# DMG_Control_Panel.net
KiCad netlist of a schematic drawn in EAGLE
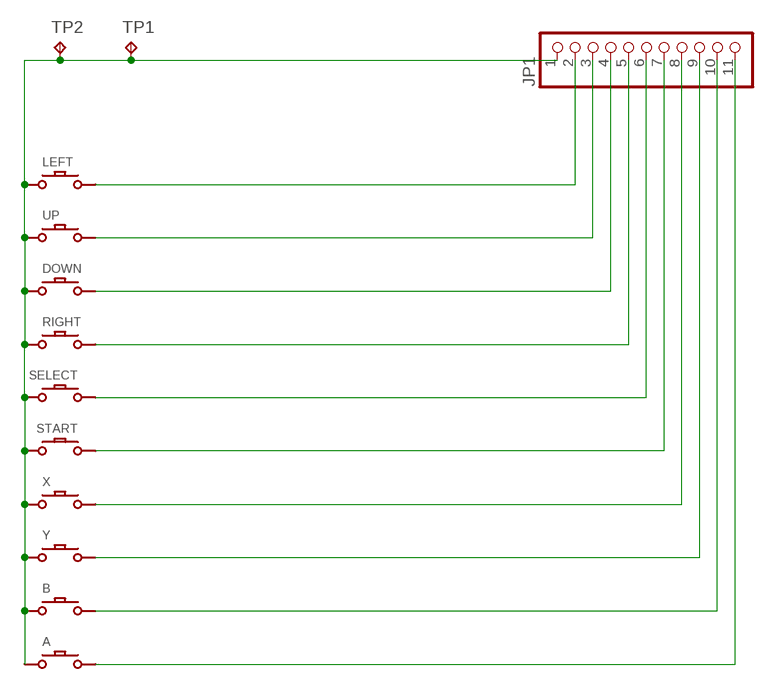
[diagram p0: schematic, sheet 1]

(export (version "E")
  (design (tool "Eeschema 10.0.6"))
  (components
    (comp (ref "A")
      (value "DMG-BTN")
      (footprint "eagle-import:DMG-BTN")
      (libsource (lib "eagle-import") (part "DMG-BTNREGULAR"))
    )
    (comp (ref "B")
      (value "DMG-BTN")
      (footprint "eagle-import:DMG-BTN")
      (libsource (lib "eagle-import") (part "DMG-BTNREGULAR"))
    )
    (comp (ref "DOWN")
      (value "DMG-BTN")
      (footprint "eagle-import:DMG-BTN")
      (libsource (lib "eagle-import") (part "DMG-BTNREGULAR"))
    )
    (comp (ref "JP1")
      (value "PINHD-1X11M")
      (footprint "eagle-import:1X11M")
      (libsource (lib "eagle-import") (part "PINHD-1X11M"))
    )
    (comp (ref "LEFT")
      (value "DMG-BTN")
      (footprint "eagle-import:DMG-BTN")
      (libsource (lib "eagle-import") (part "DMG-BTNREGULAR"))
    )
    (comp (ref "RIGHT")
      (value "DMG-BTN")
      (footprint "eagle-import:DMG-BTN")
      (libsource (lib "eagle-import") (part "DMG-BTNREGULAR"))
    )
    (comp (ref "SELECT")
      (value "DMG-BTN")
      (footprint "eagle-import:DMG-SEL")
      (libsource (lib "eagle-import") (part "DMG-BTNSELECT"))
    )
    (comp (ref "START")
      (value "DMG-BTN")
      (footprint "eagle-import:DMG-SEL")
      (libsource (lib "eagle-import") (part "DMG-BTNSELECT"))
    )
    (comp (ref "TP1")
      (value "TPPAD1-13Y")
      (footprint "eagle-import:P1-13Y")
      (libsource (lib "eagle-import") (part "TPPAD1-13Y"))
    )
    (comp (ref "TP2")
      (value "TPPAD1-13Y")
      (footprint "eagle-import:P1-13Y")
      (libsource (lib "eagle-import") (part "TPPAD1-13Y"))
    )
    (comp (ref "UP")
      (value "DMG-BTN")
      (footprint "eagle-import:DMG-BTN")
      (libsource (lib "eagle-import") (part "DMG-BTNREGULAR"))
    )
    (comp (ref "X")
      (value "DMG-BTN")
      (footprint "eagle-import:DMG-BTN")
      (libsource (lib "eagle-import") (part "DMG-BTNREGULAR"))
    )
    (comp (ref "Y")
      (value "DMG-BTN")
      (footprint "eagle-import:DMG-BTN")
      (libsource (lib "eagle-import") (part "DMG-BTNREGULAR"))
    )
  )
  (nets
    (net (code "1") (name "Net-(A-PadP$1)") (class "Default")
      (node (ref "A") (pin "P$1") (pinfunction "P$1_P$1") (pintype "bidirectional"))
      (node (ref "B") (pin "P$1") (pinfunction "P$1_P$1") (pintype "bidirectional"))
      (node (ref "DOWN") (pin "P$1") (pinfunction "P$1_P$1") (pintype "bidirectional"))
      (node (ref "JP1") (pin "1") (pinfunction "1_1") (pintype "passive"))
      (node (ref "LEFT") (pin "P$1") (pinfunction "P$1_P$1") (pintype "bidirectional"))
      (node (ref "RIGHT") (pin "P$1") (pinfunction "P$1_P$1") (pintype "bidirectional"))
      (node (ref "SELECT") (pin "P$2") (pinfunction "P$2_P$2") (pintype "bidirectional"))
      (node (ref "START") (pin "P$2") (pinfunction "P$2_P$2") (pintype "bidirectional"))
      (node (ref "TP1") (pin "TP") (pinfunction "TP_TP") (pintype "input"))
      (node (ref "TP2") (pin "TP") (pinfunction "TP_TP") (pintype "input"))
      (node (ref "UP") (pin "P$1") (pinfunction "P$1_P$1") (pintype "bidirectional"))
      (node (ref "X") (pin "P$1") (pinfunction "P$1_P$1") (pintype "bidirectional"))
      (node (ref "Y") (pin "P$1") (pinfunction "P$1_P$1") (pintype "bidirectional"))
    )
    (net (code "2") (name "Net-(A-PadP$2)") (class "Default")
      (node (ref "A") (pin "P$2") (pinfunction "P$2_P$2") (pintype "bidirectional"))
      (node (ref "JP1") (pin "11") (pinfunction "11_11") (pintype "passive"))
    )
    (net (code "3") (name "Net-(B-PadP$2)") (class "Default")
      (node (ref "B") (pin "P$2") (pinfunction "P$2_P$2") (pintype "bidirectional"))
      (node (ref "JP1") (pin "10") (pinfunction "10_10") (pintype "passive"))
    )
    (net (code "4") (name "Net-(DOWN-PadP$2)") (class "Default")
      (node (ref "DOWN") (pin "P$2") (pinfunction "P$2_P$2") (pintype "bidirectional"))
      (node (ref "JP1") (pin "4") (pinfunction "4_4") (pintype "passive"))
    )
    (net (code "5") (name "Net-(JP1-Pad2)") (class "Default")
      (node (ref "JP1") (pin "2") (pinfunction "2_2") (pintype "passive"))
      (node (ref "LEFT") (pin "P$2") (pinfunction "P$2_P$2") (pintype "bidirectional"))
    )
    (net (code "6") (name "Net-(JP1-Pad3)") (class "Default")
      (node (ref "JP1") (pin "3") (pinfunction "3_3") (pintype "passive"))
      (node (ref "UP") (pin "P$2") (pinfunction "P$2_P$2") (pintype "bidirectional"))
    )
    (net (code "7") (name "Net-(JP1-Pad5)") (class "Default")
      (node (ref "JP1") (pin "5") (pinfunction "5_5") (pintype "passive"))
      (node (ref "RIGHT") (pin "P$2") (pinfunction "P$2_P$2") (pintype "bidirectional"))
    )
    (net (code "8") (name "Net-(JP1-Pad6)") (class "Default")
      (node (ref "JP1") (pin "6") (pinfunction "6_6") (pintype "passive"))
      (node (ref "SELECT") (pin "P$1") (pinfunction "P$1_P$1") (pintype "bidirectional"))
    )
    (net (code "9") (name "Net-(JP1-Pad7)") (class "Default")
      (node (ref "JP1") (pin "7") (pinfunction "7_7") (pintype "passive"))
      (node (ref "START") (pin "P$1") (pinfunction "P$1_P$1") (pintype "bidirectional"))
    )
    (net (code "10") (name "Net-(JP1-Pad8)") (class "Default")
      (node (ref "JP1") (pin "8") (pinfunction "8_8") (pintype "passive"))
      (node (ref "X") (pin "P$2") (pinfunction "P$2_P$2") (pintype "bidirectional"))
    )
    (net (code "11") (name "Net-(JP1-Pad9)") (class "Default")
      (node (ref "JP1") (pin "9") (pinfunction "9_9") (pintype "passive"))
      (node (ref "Y") (pin "P$2") (pinfunction "P$2_P$2") (pintype "bidirectional"))
    )
  )
)
